# pyPhotometry_2_0.net
KiCad netlist of a schematic drawn in EAGLE
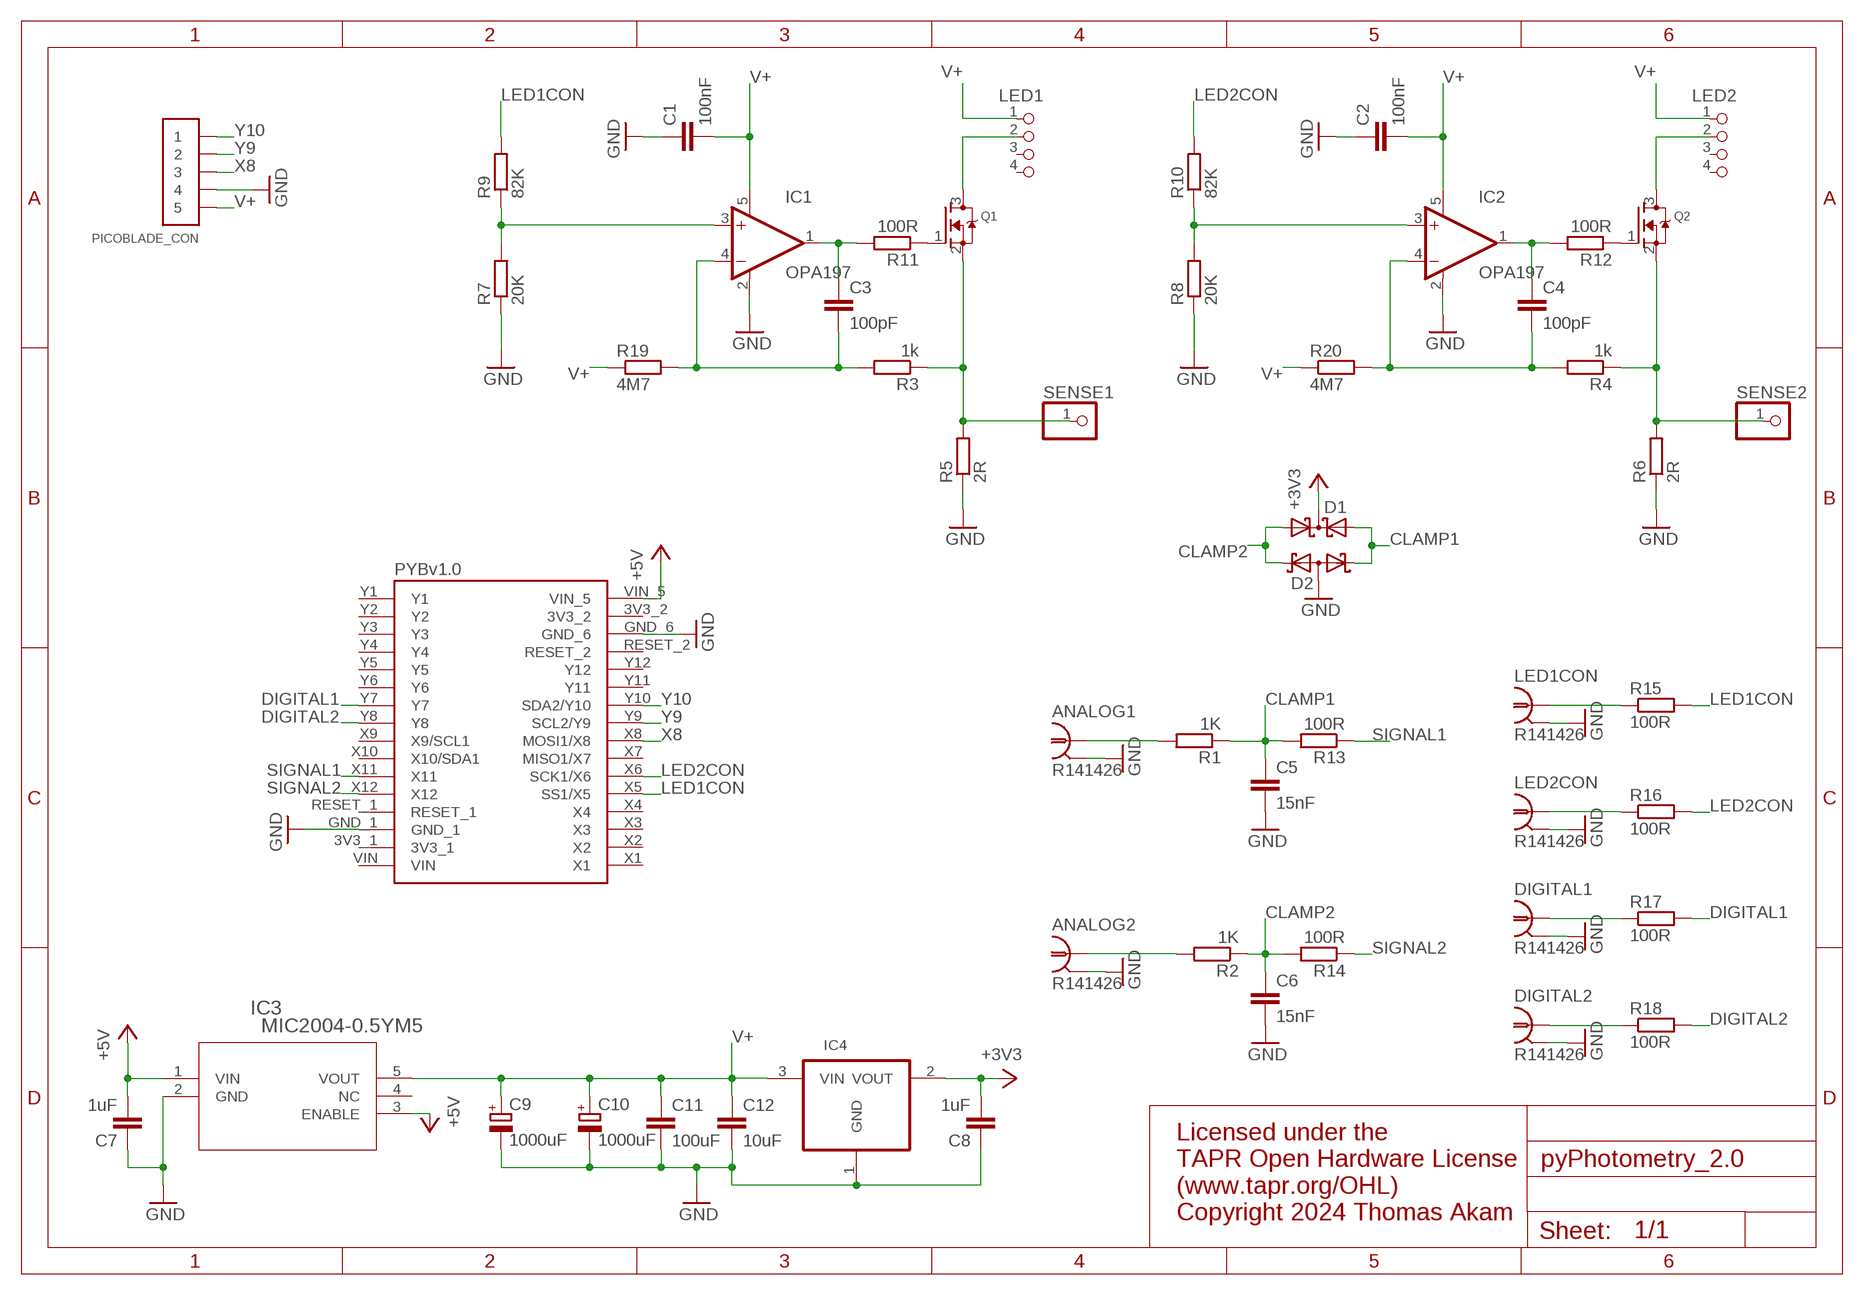
[diagram p0: schematic, sheet 1]

(export (version "E")
  (design (tool "Eeschema 10.0.6"))
  (components
    (comp (ref "ANALOG1")
      (value "R141426")
      (footprint "eagle-import:R141426")
      (fields (field (name "MF") "FARNELL") (field (name "MPN") "R141426161"))
      (libsource (lib "eagle-import") (part "R141426"))
    )
    (comp (ref "ANALOG2")
      (value "R141426")
      (footprint "eagle-import:R141426")
      (fields (field (name "MF") "FARNELL") (field (name "MPN") "R141426161"))
      (libsource (lib "eagle-import") (part "R141426"))
    )
    (comp (ref "C1")
      (value "100nF")
      (footprint "eagle-import:C0603K")
      (libsource (lib "eagle-import") (part "C-EUC0603K"))
    )
    (comp (ref "C2")
      (value "100nF")
      (footprint "eagle-import:C0603")
      (libsource (lib "eagle-import") (part "C-EUC0603"))
    )
    (comp (ref "C3")
      (value "100pF")
      (footprint "eagle-import:C0603K")
      (libsource (lib "eagle-import") (part "C-EUC0603K"))
    )
    (comp (ref "C4")
      (value "100pF")
      (footprint "eagle-import:C0603K")
      (libsource (lib "eagle-import") (part "C-EUC0603K"))
    )
    (comp (ref "C5")
      (value "15nF")
      (footprint "eagle-import:C0603K")
      (libsource (lib "eagle-import") (part "C-EUC0603K"))
    )
    (comp (ref "C6")
      (value "15nF")
      (footprint "eagle-import:C0603K")
      (libsource (lib "eagle-import") (part "C-EUC0603K"))
    )
    (comp (ref "C7")
      (value "1uF")
      (footprint "eagle-import:C0603")
      (libsource (lib "eagle-import") (part "C-EUC0603"))
    )
    (comp (ref "C8")
      (value "1uF")
      (footprint "eagle-import:C0603")
      (libsource (lib "eagle-import") (part "C-EUC0603"))
    )
    (comp (ref "C9")
      (value "1000uF")
      (footprint "eagle-import:153CLV-0807")
      (libsource (lib "eagle-import") (part "CPOL-EU153CLV-0807"))
    )
    (comp (ref "C10")
      (value "1000uF")
      (footprint "eagle-import:153CLV-0807")
      (libsource (lib "eagle-import") (part "CPOL-EU153CLV-0807"))
    )
    (comp (ref "C11")
      (value "100uF")
      (footprint "eagle-import:C1206")
      (libsource (lib "eagle-import") (part "C-EUC1206"))
    )
    (comp (ref "C12")
      (value "10uF")
      (footprint "eagle-import:C1206")
      (libsource (lib "eagle-import") (part "C-EUC1206"))
    )
    (comp (ref "D1")
      (value "BAT54C")
      (footprint "eagle-import:SOT23")
      (libsource (lib "eagle-import") (part "BAT54C"))
    )
    (comp (ref "D2")
      (value "BAT54A")
      (footprint "eagle-import:SOT23")
      (libsource (lib "eagle-import") (part "BAT54A"))
    )
    (comp (ref "DIGITAL1")
      (value "R141426")
      (footprint "eagle-import:R141426")
      (fields (field (name "MF") "FARNELL") (field (name "MPN") "R141426161"))
      (libsource (lib "eagle-import") (part "R141426"))
    )
    (comp (ref "DIGITAL2")
      (value "R141426")
      (footprint "eagle-import:R141426")
      (fields (field (name "MF") "FARNELL") (field (name "MPN") "R141426161"))
      (libsource (lib "eagle-import") (part "R141426"))
    )
    (comp (ref "IC1")
      (value "OPA197")
      (footprint "eagle-import:SOT23-5")
      (libsource (lib "eagle-import") (part "OPA197"))
    )
    (comp (ref "IC2")
      (value "OPA197")
      (footprint "eagle-import:SOT23-5")
      (libsource (lib "eagle-import") (part "OPA197"))
    )
    (comp (ref "IC3")
      (value "MIC2004-0.5YM5")
      (footprint "eagle-import:SOT-23-5_M5")
      (fields (field (name "MANUFACTURER_PART_NUMBER") "MIC20040.5YM5"))
      (libsource (lib "eagle-import") (part "MIC2004-0.5YM5"))
    )
    (comp (ref "IC4")
      (value "MCP1700T-3302E/TT")
      (footprint "eagle-import:SOT95P237X112-3N")
      (libsource (lib "eagle-import") (part "MCP1700T-3302E/TT"))
    )
    (comp (ref "LED1")
      (value "M8-4")
      (footprint "eagle-import:M8-4")
      (libsource (lib "eagle-import") (part "M8-4"))
    )
    (comp (ref "LED1CON")
      (value "R141426")
      (footprint "eagle-import:R141426")
      (fields (field (name "MF") "FARNELL") (field (name "MPN") "R141426161"))
      (libsource (lib "eagle-import") (part "R141426"))
    )
    (comp (ref "LED2")
      (value "M8-4")
      (footprint "eagle-import:M8-4")
      (libsource (lib "eagle-import") (part "M8-4"))
    )
    (comp (ref "LED2CON")
      (value "R141426")
      (footprint "eagle-import:R141426")
      (fields (field (name "MF") "FARNELL") (field (name "MPN") "R141426161"))
      (libsource (lib "eagle-import") (part "R141426"))
    )
    (comp (ref "PICOBLADE_CON")
      (value "CONN_5-1-53261")
      (footprint "eagle-import:PB-53261-05")
      (libsource (lib "eagle-import") (part "CONN_5-1-53261"))
    )
    (comp (ref "Q1")
      (value "MOSFET-NREFLOW")
      (footprint "eagle-import:SOT23")
      (libsource (lib "eagle-import") (part "MOSFET-NREFLOW"))
    )
    (comp (ref "Q2")
      (value "MOSFET-NREFLOW")
      (footprint "eagle-import:SOT23")
      (libsource (lib "eagle-import") (part "MOSFET-NREFLOW"))
    )
    (comp (ref "R1")
      (value "1K")
      (footprint "eagle-import:R0603")
      (libsource (lib "eagle-import") (part "R-EU_R0603"))
    )
    (comp (ref "R2")
      (value "1K")
      (footprint "eagle-import:R0603")
      (libsource (lib "eagle-import") (part "R-EU_R0603"))
    )
    (comp (ref "R3")
      (value "1k")
      (footprint "eagle-import:R0603")
      (libsource (lib "eagle-import") (part "R-EU_R0603"))
    )
    (comp (ref "R4")
      (value "1k")
      (footprint "eagle-import:R0603")
      (libsource (lib "eagle-import") (part "R-EU_R0603"))
    )
    (comp (ref "R5")
      (value "2R")
      (footprint "eagle-import:R0603")
      (libsource (lib "eagle-import") (part "R-EU_R0603"))
    )
    (comp (ref "R6")
      (value "2R")
      (footprint "eagle-import:R0603")
      (libsource (lib "eagle-import") (part "R-EU_R0603"))
    )
    (comp (ref "R7")
      (value "20K")
      (footprint "eagle-import:R0603")
      (libsource (lib "eagle-import") (part "R-EU_R0603"))
    )
    (comp (ref "R8")
      (value "20K")
      (footprint "eagle-import:R0603")
      (libsource (lib "eagle-import") (part "R-EU_R0603"))
    )
    (comp (ref "R9")
      (value "82K")
      (footprint "eagle-import:R0603")
      (libsource (lib "eagle-import") (part "R-EU_R0603"))
    )
    (comp (ref "R10")
      (value "82K")
      (footprint "eagle-import:R0603")
      (libsource (lib "eagle-import") (part "R-EU_R0603"))
    )
    (comp (ref "R11")
      (value "100R")
      (footprint "eagle-import:R0603")
      (libsource (lib "eagle-import") (part "R-EU_R0603"))
    )
    (comp (ref "R12")
      (value "100R")
      (footprint "eagle-import:R0603")
      (libsource (lib "eagle-import") (part "R-EU_R0603"))
    )
    (comp (ref "R13")
      (value "100R")
      (footprint "eagle-import:R0603")
      (libsource (lib "eagle-import") (part "R-EU_R0603"))
    )
    (comp (ref "R14")
      (value "100R")
      (footprint "eagle-import:R0603")
      (libsource (lib "eagle-import") (part "R-EU_R0603"))
    )
    (comp (ref "R15")
      (value "100R")
      (footprint "eagle-import:R0603")
      (libsource (lib "eagle-import") (part "R-EU_R0603"))
    )
    (comp (ref "R16")
      (value "100R")
      (footprint "eagle-import:R0603")
      (libsource (lib "eagle-import") (part "R-EU_R0603"))
    )
    (comp (ref "R17")
      (value "100R")
      (footprint "eagle-import:R0603")
      (libsource (lib "eagle-import") (part "R-EU_R0603"))
    )
    (comp (ref "R18")
      (value "100R")
      (footprint "eagle-import:R0603")
      (libsource (lib "eagle-import") (part "R-EU_R0603"))
    )
    (comp (ref "R19")
      (value "4M7")
      (footprint "eagle-import:R0603")
      (libsource (lib "eagle-import") (part "R-EU_R0603"))
    )
    (comp (ref "R20")
      (value "4M7")
      (footprint "eagle-import:R0603")
      (libsource (lib "eagle-import") (part "R-EU_R0603"))
    )
    (comp (ref "SENSE1")
      (value "PINHD-1X1")
      (footprint "eagle-import:1X01")
      (libsource (lib "eagle-import") (part "PINHD-1X1"))
    )
    (comp (ref "SENSE2")
      (value "PINHD-1X1")
      (footprint "eagle-import:1X01")
      (libsource (lib "eagle-import") (part "PINHD-1X1"))
    )
    (comp (ref "U$1")
      (value "PYBOARD-REDUCED-3")
      (footprint "eagle-import:PYBOARD-REDUCED-3")
      (libsource (lib "eagle-import") (part "PYBOARD-REDUCED-3"))
    )
  )
  (nets
    (net (code "1") (name "+3V3") (class "Default")
      (node (ref "C8") (pin "2") (pinfunction "2_2") (pintype "passive"))
      (node (ref "D1") (pin "3") (pinfunction "CC_3") (pintype "passive"))
      (node (ref "IC4") (pin "2") (pinfunction "VOUT_2") (pintype "output"))
    )
    (net (code "2") (name "+5V") (class "Default")
      (node (ref "C7") (pin "2") (pinfunction "2_2") (pintype "passive"))
      (node (ref "IC3") (pin "1") (pinfunction "VIN_1") (pintype "input"))
      (node (ref "IC3") (pin "3") (pinfunction "ENABLE_3") (pintype "input"))
      (node (ref "U$1") (pin "VIN_5") (pinfunction "VIN_5_VIN_5") (pintype "bidirectional"))
    )
    (net (code "3") (name "/CLAMP1") (class "Default")
      (node (ref "C5") (pin "1") (pinfunction "1_1") (pintype "passive"))
      (node (ref "D1") (pin "2") (pinfunction "A2_2") (pintype "passive"))
      (node (ref "D2") (pin "1") (pinfunction "K1_1") (pintype "passive"))
      (node (ref "R1") (pin "1") (pinfunction "1_1") (pintype "passive"))
      (node (ref "R13") (pin "2") (pinfunction "2_2") (pintype "passive"))
    )
    (net (code "4") (name "/CLAMP2") (class "Default")
      (node (ref "C6") (pin "1") (pinfunction "1_1") (pintype "passive"))
      (node (ref "D1") (pin "1") (pinfunction "A1_1") (pintype "passive"))
      (node (ref "D2") (pin "2") (pinfunction "K2_2") (pintype "passive"))
      (node (ref "R14") (pin "2") (pinfunction "2_2") (pintype "passive"))
      (node (ref "R2") (pin "1") (pinfunction "1_1") (pintype "passive"))
    )
    (net (code "5") (name "/DIGITAL1") (class "Default")
      (node (ref "R17") (pin "2") (pinfunction "2_2") (pintype "passive"))
      (node (ref "U$1") (pin "Y7") (pinfunction "Y7_Y7") (pintype "bidirectional"))
    )
    (net (code "6") (name "/DIGITAL2") (class "Default")
      (node (ref "R18") (pin "2") (pinfunction "2_2") (pintype "passive"))
      (node (ref "U$1") (pin "Y8") (pinfunction "Y8_Y8") (pintype "bidirectional"))
    )
    (net (code "7") (name "/LED1CON") (class "Default")
      (node (ref "R15") (pin "2") (pinfunction "2_2") (pintype "passive"))
      (node (ref "R9") (pin "2") (pinfunction "2_2") (pintype "passive"))
      (node (ref "U$1") (pin "X5") (pinfunction "SS1/X5_X5") (pintype "bidirectional"))
    )
    (net (code "8") (name "/LED2CON") (class "Default")
      (node (ref "R10") (pin "2") (pinfunction "2_2") (pintype "passive"))
      (node (ref "R16") (pin "2") (pinfunction "2_2") (pintype "passive"))
      (node (ref "U$1") (pin "X6") (pinfunction "SCK1/X6_X6") (pintype "bidirectional"))
    )
    (net (code "9") (name "/SIGNAL1") (class "Default")
      (node (ref "R13") (pin "1") (pinfunction "1_1") (pintype "passive"))
      (node (ref "U$1") (pin "X11") (pinfunction "X11_X11") (pintype "bidirectional"))
    )
    (net (code "10") (name "/SIGNAL2") (class "Default")
      (node (ref "R14") (pin "1") (pinfunction "1_1") (pintype "passive"))
      (node (ref "U$1") (pin "X12") (pinfunction "X12_X12") (pintype "bidirectional"))
    )
    (net (code "11") (name "/V+") (class "Default")
      (node (ref "C1") (pin "2") (pinfunction "2_2") (pintype "passive"))
      (node (ref "C10") (pin "+") (pinfunction "+_+") (pintype "passive"))
      (node (ref "C11") (pin "1") (pinfunction "1_1") (pintype "passive"))
      (node (ref "C12") (pin "1") (pinfunction "1_1") (pintype "passive"))
      (node (ref "C2") (pin "2") (pinfunction "2_2") (pintype "passive"))
      (node (ref "C9") (pin "+") (pinfunction "+_+") (pintype "passive"))
      (node (ref "IC1") (pin "5") (pinfunction "V+_5") (pintype "power_in"))
      (node (ref "IC2") (pin "5") (pinfunction "V+_5") (pintype "power_in"))
      (node (ref "IC3") (pin "5") (pinfunction "VOUT_5") (pintype "output"))
      (node (ref "IC4") (pin "3") (pinfunction "VIN_3") (pintype "input"))
      (node (ref "LED1") (pin "1") (pinfunction "1_1") (pintype "passive"))
      (node (ref "LED2") (pin "1") (pinfunction "1_1") (pintype "passive"))
      (node (ref "PICOBLADE_CON") (pin "5") (pinfunction "5_5") (pintype "bidirectional"))
      (node (ref "R19") (pin "1") (pinfunction "1_1") (pintype "passive"))
      (node (ref "R20") (pin "1") (pinfunction "1_1") (pintype "passive"))
    )
    (net (code "12") (name "/X8") (class "Default")
      (node (ref "PICOBLADE_CON") (pin "3") (pinfunction "3_3") (pintype "bidirectional"))
      (node (ref "U$1") (pin "X8") (pinfunction "MOSI1/X8_X8") (pintype "bidirectional"))
    )
    (net (code "13") (name "/Y9") (class "Default")
      (node (ref "PICOBLADE_CON") (pin "2") (pinfunction "2_2") (pintype "bidirectional"))
      (node (ref "U$1") (pin "Y9") (pinfunction "SCL2/Y9_Y9") (pintype "bidirectional"))
    )
    (net (code "14") (name "/Y10") (class "Default")
      (node (ref "PICOBLADE_CON") (pin "1") (pinfunction "1_1") (pintype "bidirectional"))
      (node (ref "U$1") (pin "Y10") (pinfunction "SDA2/Y10_Y10") (pintype "bidirectional"))
    )
    (net (code "15") (name "GND") (class "Default")
      (node (ref "ANALOG1") (pin "2") (pinfunction "GND_2") (pintype "power_in"))
      (node (ref "ANALOG2") (pin "2") (pinfunction "GND_2") (pintype "power_in"))
      (node (ref "C1") (pin "1") (pinfunction "1_1") (pintype "passive"))
      (node (ref "C10") (pin "-") (pinfunction "-_-") (pintype "passive"))
      (node (ref "C11") (pin "2") (pinfunction "2_2") (pintype "passive"))
      (node (ref "C12") (pin "2") (pinfunction "2_2") (pintype "passive"))
      (node (ref "C2") (pin "1") (pinfunction "1_1") (pintype "passive"))
      (node (ref "C5") (pin "2") (pinfunction "2_2") (pintype "passive"))
      (node (ref "C6") (pin "2") (pinfunction "2_2") (pintype "passive"))
      (node (ref "C7") (pin "1") (pinfunction "1_1") (pintype "passive"))
      (node (ref "C8") (pin "1") (pinfunction "1_1") (pintype "passive"))
      (node (ref "C9") (pin "-") (pinfunction "-_-") (pintype "passive"))
      (node (ref "D2") (pin "3") (pinfunction "AA_3") (pintype "passive"))
      (node (ref "DIGITAL1") (pin "2") (pinfunction "GND_2") (pintype "power_in"))
      (node (ref "DIGITAL2") (pin "2") (pinfunction "GND_2") (pintype "power_in"))
      (node (ref "IC1") (pin "2") (pinfunction "V-_2") (pintype "power_in"))
      (node (ref "IC2") (pin "2") (pinfunction "V-_2") (pintype "power_in"))
      (node (ref "IC3") (pin "2") (pinfunction "GND_2") (pintype "power_in"))
      (node (ref "IC4") (pin "1") (pinfunction "GND_1") (pintype "passive"))
      (node (ref "LED1CON") (pin "2") (pinfunction "GND_2") (pintype "power_in"))
      (node (ref "LED2CON") (pin "2") (pinfunction "GND_2") (pintype "power_in"))
      (node (ref "PICOBLADE_CON") (pin "4") (pinfunction "4_4") (pintype "bidirectional"))
      (node (ref "R5") (pin "1") (pinfunction "1_1") (pintype "passive"))
      (node (ref "R6") (pin "1") (pinfunction "1_1") (pintype "passive"))
      (node (ref "R7") (pin "1") (pinfunction "1_1") (pintype "passive"))
      (node (ref "R8") (pin "1") (pinfunction "1_1") (pintype "passive"))
      (node (ref "U$1") (pin "GND_1") (pinfunction "GND_1_GND_1") (pintype "bidirectional"))
      (node (ref "U$1") (pin "GND_6") (pinfunction "GND_6_GND_6") (pintype "bidirectional"))
    )
    (net (code "16") (name "Net-(ANALOG1-Pad1)") (class "Default")
      (node (ref "ANALOG1") (pin "1") (pinfunction "1_1") (pintype "passive"))
      (node (ref "R1") (pin "2") (pinfunction "2_2") (pintype "passive"))
    )
    (net (code "17") (name "Net-(ANALOG2-Pad1)") (class "Default")
      (node (ref "ANALOG2") (pin "1") (pinfunction "1_1") (pintype "passive"))
      (node (ref "R2") (pin "2") (pinfunction "2_2") (pintype "passive"))
    )
    (net (code "18") (name "Net-(DIGITAL1-Pad1)") (class "Default")
      (node (ref "DIGITAL1") (pin "1") (pinfunction "1_1") (pintype "passive"))
      (node (ref "R17") (pin "1") (pinfunction "1_1") (pintype "passive"))
    )
    (net (code "19") (name "Net-(DIGITAL2-Pad1)") (class "Default")
      (node (ref "DIGITAL2") (pin "1") (pinfunction "1_1") (pintype "passive"))
      (node (ref "R18") (pin "1") (pinfunction "1_1") (pintype "passive"))
    )
    (net (code "20") (name "Net-(IC1-+IN)") (class "Default")
      (node (ref "IC1") (pin "3") (pinfunction "+IN_3") (pintype "input"))
      (node (ref "R7") (pin "2") (pinfunction "2_2") (pintype "passive"))
      (node (ref "R9") (pin "1") (pinfunction "1_1") (pintype "passive"))
    )
    (net (code "21") (name "Net-(IC1--IN)") (class "Default")
      (node (ref "C3") (pin "2") (pinfunction "2_2") (pintype "passive"))
      (node (ref "IC1") (pin "4") (pinfunction "-IN_4") (pintype "input"))
      (node (ref "R19") (pin "2") (pinfunction "2_2") (pintype "passive"))
      (node (ref "R3") (pin "2") (pinfunction "2_2") (pintype "passive"))
    )
    (net (code "22") (name "Net-(IC1-OUT)") (class "Default")
      (node (ref "C3") (pin "1") (pinfunction "1_1") (pintype "passive"))
      (node (ref "IC1") (pin "1") (pinfunction "OUT_1") (pintype "output"))
      (node (ref "R11") (pin "2") (pinfunction "2_2") (pintype "passive"))
    )
    (net (code "23") (name "Net-(IC2-+IN)") (class "Default")
      (node (ref "IC2") (pin "3") (pinfunction "+IN_3") (pintype "input"))
      (node (ref "R10") (pin "1") (pinfunction "1_1") (pintype "passive"))
      (node (ref "R8") (pin "2") (pinfunction "2_2") (pintype "passive"))
    )
    (net (code "24") (name "Net-(IC2--IN)") (class "Default")
      (node (ref "C4") (pin "2") (pinfunction "2_2") (pintype "passive"))
      (node (ref "IC2") (pin "4") (pinfunction "-IN_4") (pintype "input"))
      (node (ref "R20") (pin "2") (pinfunction "2_2") (pintype "passive"))
      (node (ref "R4") (pin "2") (pinfunction "2_2") (pintype "passive"))
    )
    (net (code "25") (name "Net-(IC2-OUT)") (class "Default")
      (node (ref "C4") (pin "1") (pinfunction "1_1") (pintype "passive"))
      (node (ref "IC2") (pin "1") (pinfunction "OUT_1") (pintype "output"))
      (node (ref "R12") (pin "2") (pinfunction "2_2") (pintype "passive"))
    )
    (net (code "26") (name "Net-(LED1CON-Pad1)") (class "Default")
      (node (ref "LED1CON") (pin "1") (pinfunction "1_1") (pintype "passive"))
      (node (ref "R15") (pin "1") (pinfunction "1_1") (pintype "passive"))
    )
    (net (code "27") (name "Net-(LED2CON-Pad1)") (class "Default")
      (node (ref "LED2CON") (pin "1") (pinfunction "1_1") (pintype "passive"))
      (node (ref "R16") (pin "1") (pinfunction "1_1") (pintype "passive"))
    )
    (net (code "28") (name "Net-(Q1-D)") (class "Default")
      (node (ref "LED1") (pin "2") (pinfunction "2_2") (pintype "passive"))
      (node (ref "Q1") (pin "3") (pinfunction "D_3") (pintype "bidirectional"))
    )
    (net (code "29") (name "Net-(Q1-G)") (class "Default")
      (node (ref "Q1") (pin "1") (pinfunction "G_1") (pintype "bidirectional"))
      (node (ref "R11") (pin "1") (pinfunction "1_1") (pintype "passive"))
    )
    (net (code "30") (name "Net-(Q1-S)") (class "Default")
      (node (ref "Q1") (pin "2") (pinfunction "S_2") (pintype "bidirectional"))
      (node (ref "R3") (pin "1") (pinfunction "1_1") (pintype "passive"))
      (node (ref "R5") (pin "2") (pinfunction "2_2") (pintype "passive"))
      (node (ref "SENSE1") (pin "1") (pinfunction "1_1") (pintype "passive"))
    )
    (net (code "31") (name "Net-(Q2-D)") (class "Default")
      (node (ref "LED2") (pin "2") (pinfunction "2_2") (pintype "passive"))
      (node (ref "Q2") (pin "3") (pinfunction "D_3") (pintype "bidirectional"))
    )
    (net (code "32") (name "Net-(Q2-G)") (class "Default")
      (node (ref "Q2") (pin "1") (pinfunction "G_1") (pintype "bidirectional"))
      (node (ref "R12") (pin "1") (pinfunction "1_1") (pintype "passive"))
    )
    (net (code "33") (name "Net-(Q2-S)") (class "Default")
      (node (ref "Q2") (pin "2") (pinfunction "S_2") (pintype "bidirectional"))
      (node (ref "R4") (pin "1") (pinfunction "1_1") (pintype "passive"))
      (node (ref "R6") (pin "2") (pinfunction "2_2") (pintype "passive"))
      (node (ref "SENSE2") (pin "1") (pinfunction "1_1") (pintype "passive"))
    )
    (net (code "34") (name "unconnected-(IC3-NC-Pad4)") (class "Default")
      (node (ref "IC3") (pin "4") (pinfunction "NC_4") (pintype "no_connect"))
    )
    (net (code "35") (name "unconnected-(LED1-Pad3)") (class "Default")
      (node (ref "LED1") (pin "3") (pinfunction "3_3") (pintype "passive"))
    )
    (net (code "36") (name "unconnected-(LED1-Pad4)") (class "Default")
      (node (ref "LED1") (pin "4") (pinfunction "4_4") (pintype "passive"))
    )
    (net (code "37") (name "unconnected-(LED2-Pad3)") (class "Default")
      (node (ref "LED2") (pin "3") (pinfunction "3_3") (pintype "passive"))
    )
    (net (code "38") (name "unconnected-(LED2-Pad4)") (class "Default")
      (node (ref "LED2") (pin "4") (pinfunction "4_4") (pintype "passive"))
    )
    (net (code "39") (name "unconnected-(U$1-MISO1{slash}X7-PadX7)") (class "Default")
      (node (ref "U$1") (pin "X7") (pinfunction "MISO1/X7_X7") (pintype "bidirectional"))
    )
    (net (code "40") (name "unconnected-(U$1-Pad3V3_1)") (class "Default")
      (node (ref "U$1") (pin "3V3_1") (pinfunction "3V3_1_3V3_1") (pintype "bidirectional"))
    )
    (net (code "41") (name "unconnected-(U$1-Pad3V3_2)") (class "Default")
      (node (ref "U$1") (pin "3V3_2") (pinfunction "3V3_2_3V3_2") (pintype "bidirectional"))
    )
    (net (code "42") (name "unconnected-(U$1-PadRESET_1)") (class "Default")
      (node (ref "U$1") (pin "RESET_1") (pinfunction "RESET_1_RESET_1") (pintype "bidirectional"))
    )
    (net (code "43") (name "unconnected-(U$1-PadRESET_2)") (class "Default")
      (node (ref "U$1") (pin "RESET_2") (pinfunction "RESET_2_RESET_2") (pintype "bidirectional"))
    )
    (net (code "44") (name "unconnected-(U$1-PadVIN)") (class "Default")
      (node (ref "U$1") (pin "VIN") (pinfunction "VIN_VIN") (pintype "bidirectional"))
    )
    (net (code "45") (name "unconnected-(U$1-PadX1)") (class "Default")
      (node (ref "U$1") (pin "X1") (pinfunction "X1_X1") (pintype "bidirectional"))
    )
    (net (code "46") (name "unconnected-(U$1-PadX2)") (class "Default")
      (node (ref "U$1") (pin "X2") (pinfunction "X2_X2") (pintype "bidirectional"))
    )
    (net (code "47") (name "unconnected-(U$1-PadX3)") (class "Default")
      (node (ref "U$1") (pin "X3") (pinfunction "X3_X3") (pintype "bidirectional"))
    )
    (net (code "48") (name "unconnected-(U$1-PadX4)") (class "Default")
      (node (ref "U$1") (pin "X4") (pinfunction "X4_X4") (pintype "bidirectional"))
    )
    (net (code "49") (name "unconnected-(U$1-PadY1)") (class "Default")
      (node (ref "U$1") (pin "Y1") (pinfunction "Y1_Y1") (pintype "bidirectional"))
    )
    (net (code "50") (name "unconnected-(U$1-PadY2)") (class "Default")
      (node (ref "U$1") (pin "Y2") (pinfunction "Y2_Y2") (pintype "bidirectional"))
    )
    (net (code "51") (name "unconnected-(U$1-PadY3)") (class "Default")
      (node (ref "U$1") (pin "Y3") (pinfunction "Y3_Y3") (pintype "bidirectional"))
    )
    (net (code "52") (name "unconnected-(U$1-PadY4)") (class "Default")
      (node (ref "U$1") (pin "Y4") (pinfunction "Y4_Y4") (pintype "bidirectional"))
    )
    (net (code "53") (name "unconnected-(U$1-PadY5)") (class "Default")
      (node (ref "U$1") (pin "Y5") (pinfunction "Y5_Y5") (pintype "bidirectional"))
    )
    (net (code "54") (name "unconnected-(U$1-PadY6)") (class "Default")
      (node (ref "U$1") (pin "Y6") (pinfunction "Y6_Y6") (pintype "bidirectional"))
    )
    (net (code "55") (name "unconnected-(U$1-PadY11)") (class "Default")
      (node (ref "U$1") (pin "Y11") (pinfunction "Y11_Y11") (pintype "bidirectional"))
    )
    (net (code "56") (name "unconnected-(U$1-PadY12)") (class "Default")
      (node (ref "U$1") (pin "Y12") (pinfunction "Y12_Y12") (pintype "bidirectional"))
    )
    (net (code "57") (name "unconnected-(U$1-X9{slash}SCL1-PadX9)") (class "Default")
      (node (ref "U$1") (pin "X9") (pinfunction "X9/SCL1_X9") (pintype "bidirectional"))
    )
    (net (code "58") (name "unconnected-(U$1-X10{slash}SDA1-PadX10)") (class "Default")
      (node (ref "U$1") (pin "X10") (pinfunction "X10/SDA1_X10") (pintype "bidirectional"))
    )
  )
)
